# ASM2028.net
KiCad netlist of a schematic drawn in EAGLE
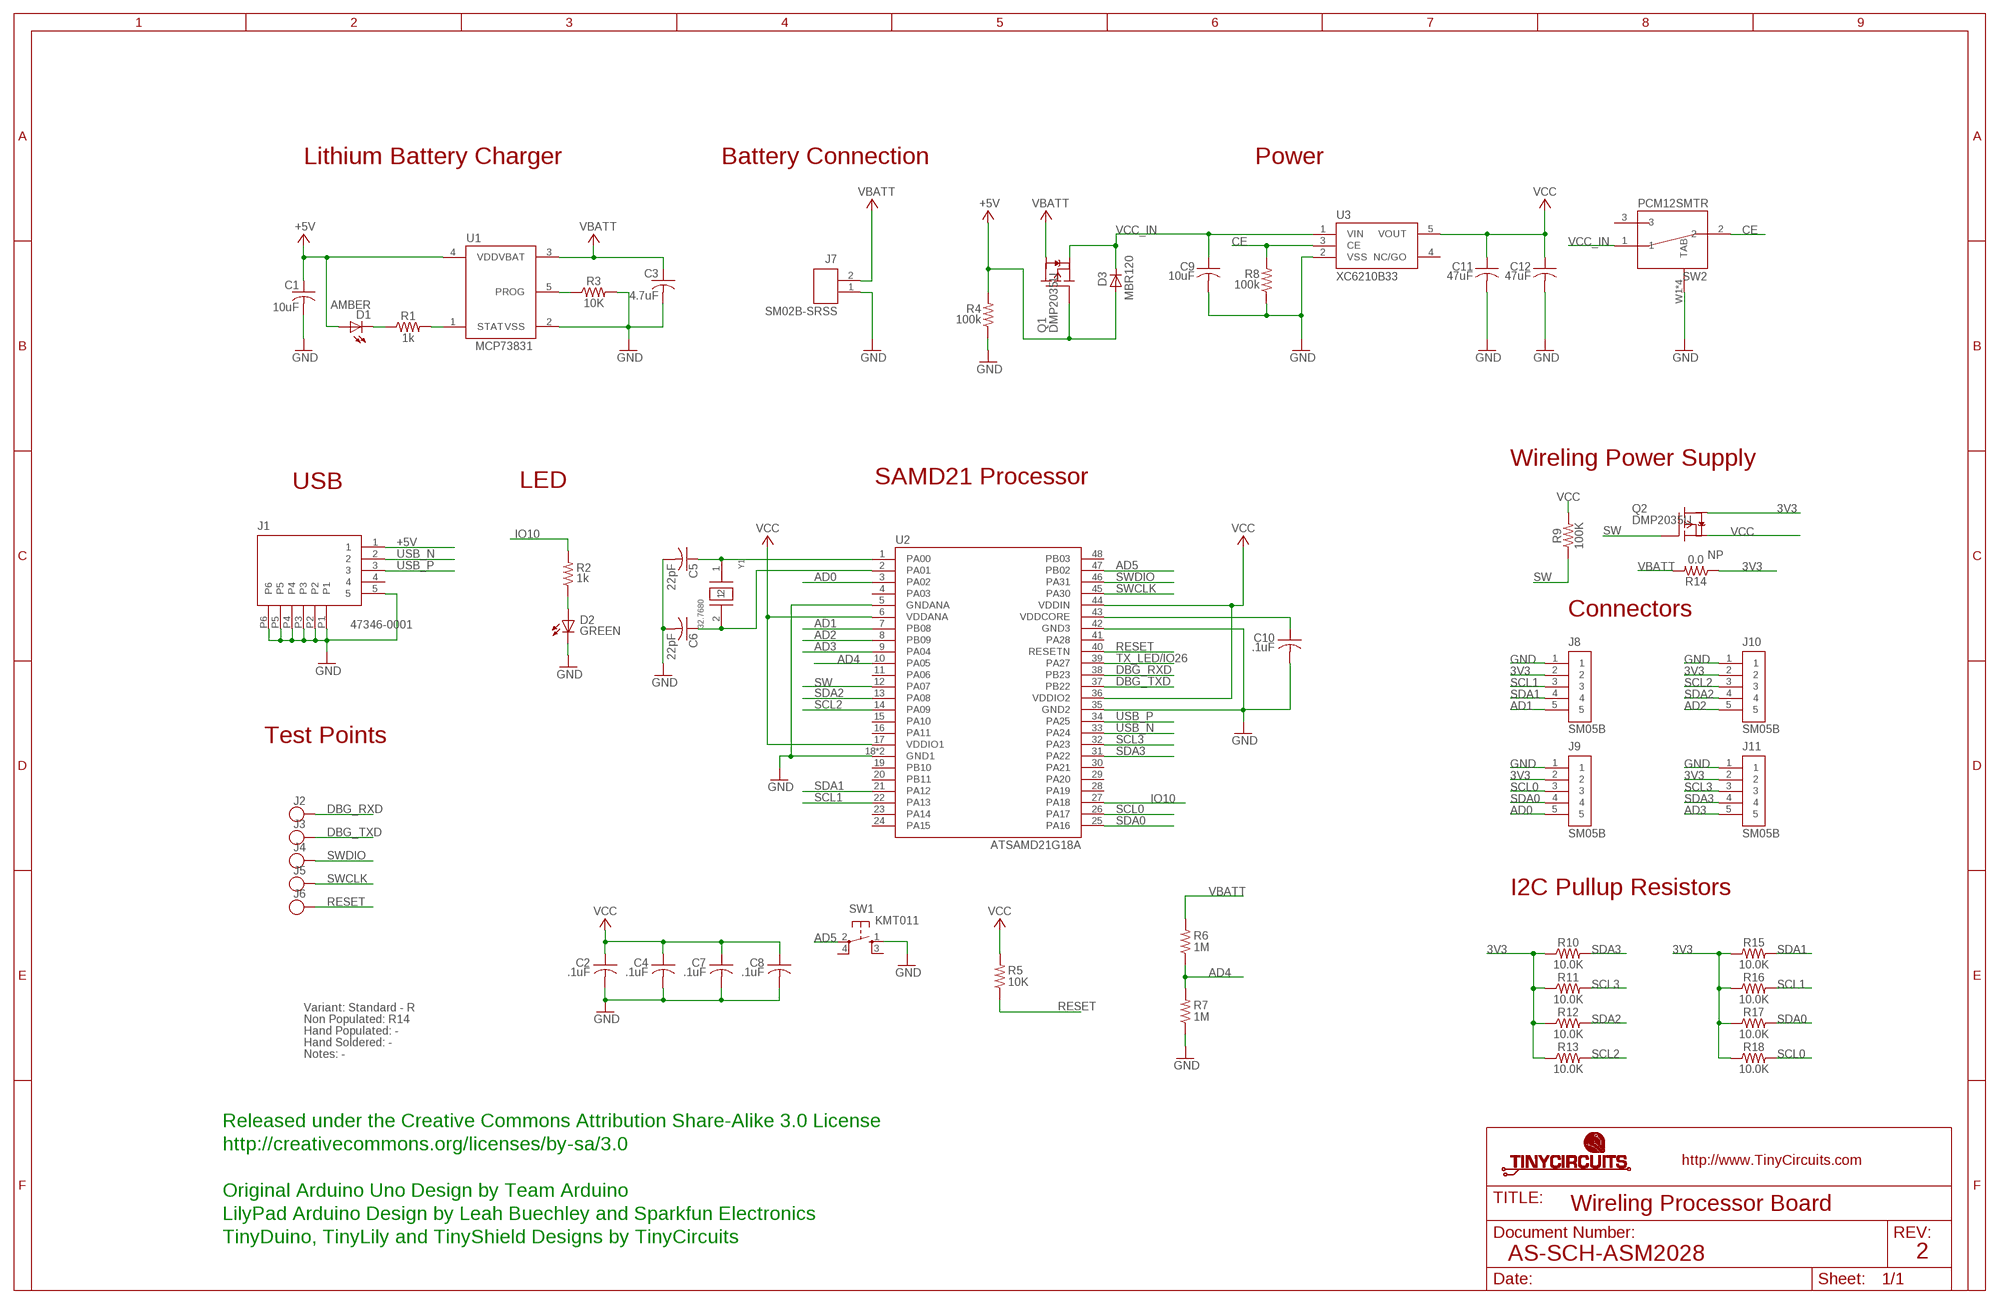
[diagram p0: schematic, sheet 1]

(export (version "E")
  (design (tool "Eeschema 10.0.6"))
  (components
    (comp (ref "C1")
      (value "10uF")
      (footprint "eagle-import:C0603")
      (fields (field (name "PARTNO") "AS-ITM-00002") (field (name "PARTNO_1") "AS-ITM-00002"))
      (libsource (lib "eagle-import") (part "AS-ITM-00002"))
    )
    (comp (ref "C2")
      (value ".1uF")
      (footprint "eagle-import:C0402")
      (fields (field (name "PARTNO") "AS-ITM-00008") (field (name "PARTNO_1") "AS-ITM-00008"))
      (libsource (lib "eagle-import") (part "AS-ITM-00008"))
    )
    (comp (ref "C3")
      (value "4.7uF")
      (footprint "eagle-import:C0603")
      (fields (field (name "PARTNO") "AS-ITM-00088") (field (name "PARTNO_1") "AS-ITM-00088"))
      (libsource (lib "eagle-import") (part "AS-ITM-00088"))
    )
    (comp (ref "C4")
      (value ".1uF")
      (footprint "eagle-import:C0402")
      (fields (field (name "PARTNO") "AS-ITM-00008") (field (name "PARTNO_1") "AS-ITM-00008"))
      (libsource (lib "eagle-import") (part "AS-ITM-00008"))
    )
    (comp (ref "C5")
      (value "22pF")
      (footprint "eagle-import:C0402")
      (fields (field (name "PARTNO") "AS-ITM-00211") (field (name "PARTNO_1") "AS-ITM-00211"))
      (libsource (lib "eagle-import") (part "AS-ITM-00211"))
    )
    (comp (ref "C6")
      (value "22pF")
      (footprint "eagle-import:C0402")
      (fields (field (name "PARTNO") "AS-ITM-00211") (field (name "PARTNO_1") "AS-ITM-00211"))
      (libsource (lib "eagle-import") (part "AS-ITM-00211"))
    )
    (comp (ref "C7")
      (value ".1uF")
      (footprint "eagle-import:C0402")
      (fields (field (name "PARTNO") "AS-ITM-00008") (field (name "PARTNO_1") "AS-ITM-00008"))
      (libsource (lib "eagle-import") (part "AS-ITM-00008"))
    )
    (comp (ref "C8")
      (value ".1uF")
      (footprint "eagle-import:C0402")
      (fields (field (name "PARTNO") "AS-ITM-00008") (field (name "PARTNO_1") "AS-ITM-00008"))
      (libsource (lib "eagle-import") (part "AS-ITM-00008"))
    )
    (comp (ref "C9")
      (value "10uF")
      (footprint "eagle-import:C0603")
      (fields (field (name "PARTNO") "AS-ITM-00002") (field (name "PARTNO_1") "AS-ITM-00002"))
      (libsource (lib "eagle-import") (part "AS-ITM-00002"))
    )
    (comp (ref "C10")
      (value ".1uF")
      (footprint "eagle-import:C0402")
      (fields (field (name "PARTNO") "AS-ITM-00008") (field (name "PARTNO_1") "AS-ITM-00008"))
      (libsource (lib "eagle-import") (part "AS-ITM-00008"))
    )
    (comp (ref "C11")
      (value "47uF")
      (footprint "eagle-import:C0603")
      (fields (field (name "PARTNO") "AS-ITM-00558") (field (name "PARTNO_1") "AS-ITM-00558"))
      (libsource (lib "eagle-import") (part "AS-ITM-00558"))
    )
    (comp (ref "C12")
      (value "47uF")
      (footprint "eagle-import:C0603")
      (fields (field (name "PARTNO") "AS-ITM-00558") (field (name "PARTNO_1") "AS-ITM-00558"))
      (libsource (lib "eagle-import") (part "AS-ITM-00558"))
    )
    (comp (ref "D1")
      (value "AMBER")
      (footprint "eagle-import:0402_LED")
      (fields (field (name "PARTNO") "AS-ITM-00058") (field (name "PARTNO_1") "AS-ITM-00058"))
      (libsource (lib "eagle-import") (part "AS-ITM-00058"))
    )
    (comp (ref "D2")
      (value "GREEN")
      (footprint "eagle-import:0402_LED")
      (fields
        (field (name "PARTNO") "AS-ITM-00038")
        (field (name "PARTNO_1") "AS-ITM-00038")
        (field (name "PNPROTATION") "0")
      )
      (libsource (lib "eagle-import") (part "AS-ITM-00038"))
    )
    (comp (ref "D3")
      (value "MBR120")
      (footprint "eagle-import:SOD-123FL")
      (fields (field (name "PARTNO") "AS-ITM-00111"))
      (libsource (lib "eagle-import") (part "AS-ITM-00111"))
    )
    (comp (ref "J1")
      (value "47346-0001")
      (footprint "eagle-import:MICRO_USB")
      (fields (field (name "PARTNO") "AS-ITM-00021"))
      (libsource (lib "eagle-import") (part "AS-ITM-00021"))
    )
    (comp (ref "J2")
      (value "TEST_POINT")
      (footprint "eagle-import:TEST_POINT_1MM")
      (libsource (lib "eagle-import") (part "TEST_POINT"))
    )
    (comp (ref "J3")
      (value "TEST_POINT")
      (footprint "eagle-import:TEST_POINT_1MM")
      (libsource (lib "eagle-import") (part "TEST_POINT"))
    )
    (comp (ref "J4")
      (value "TEST_POINT")
      (footprint "eagle-import:TEST_POINT_1MM")
      (libsource (lib "eagle-import") (part "TEST_POINT"))
    )
    (comp (ref "J5")
      (value "TEST_POINT")
      (footprint "eagle-import:TEST_POINT_1MM")
      (libsource (lib "eagle-import") (part "TEST_POINT"))
    )
    (comp (ref "J6")
      (value "TEST_POINT")
      (footprint "eagle-import:TEST_POINT_1MM")
      (libsource (lib "eagle-import") (part "TEST_POINT"))
    )
    (comp (ref "J7")
      (value "SM02B-SRSS")
      (footprint "eagle-import:JST_SH_2X1")
      (fields (field (name "PARTNO") "AS-ITM-00231"))
      (libsource (lib "eagle-import") (part "AS-ITM-00231"))
    )
    (comp (ref "J8")
      (value "SM05B")
      (footprint "eagle-import:JST_SH_5X1_EDGE")
      (fields (field (name "PARTNO") "AS-ITM-00340"))
      (libsource (lib "eagle-import") (part "AS-ITM-00340EDGE"))
    )
    (comp (ref "J9")
      (value "SM05B")
      (footprint "eagle-import:JST_SH_5X1_EDGE")
      (fields (field (name "PARTNO") "AS-ITM-00340"))
      (libsource (lib "eagle-import") (part "AS-ITM-00340EDGE"))
    )
    (comp (ref "J10")
      (value "SM05B")
      (footprint "eagle-import:JST_SH_5X1_EDGE")
      (fields (field (name "PARTNO") "AS-ITM-00340"))
      (libsource (lib "eagle-import") (part "AS-ITM-00340EDGE"))
    )
    (comp (ref "J11")
      (value "SM05B")
      (footprint "eagle-import:JST_SH_5X1_EDGE")
      (fields (field (name "PARTNO") "AS-ITM-00340"))
      (libsource (lib "eagle-import") (part "AS-ITM-00340EDGE"))
    )
    (comp (ref "Q1")
      (value "DMP2035U")
      (footprint "eagle-import:SOT23A")
      (fields (field (name "PARTNO") "AS-ITM-00024"))
      (libsource (lib "eagle-import") (part "AS-ITM-00024A"))
    )
    (comp (ref "Q2")
      (value "DMP2035U")
      (footprint "eagle-import:SOT23A")
      (fields (field (name "PARTNO") "AS-ITM-00024") (field (name "PARTNO_1") "AS-ITM-00024"))
      (libsource (lib "eagle-import") (part "AS-ITM-00024A"))
    )
    (comp (ref "R1")
      (value "1k")
      (footprint "eagle-import:0402")
      (fields (field (name "PARTNO") "AS-ITM-00003") (field (name "PARTNO_1") "AS-ITM-00003"))
      (libsource (lib "eagle-import") (part "AS-ITM-00003"))
    )
    (comp (ref "R2")
      (value "1k")
      (footprint "eagle-import:0402")
      (fields (field (name "PARTNO") "AS-ITM-00003") (field (name "PARTNO_1") "AS-ITM-00003"))
      (libsource (lib "eagle-import") (part "AS-ITM-00003"))
    )
    (comp (ref "R3")
      (value "10K")
      (footprint "eagle-import:0402")
      (fields (field (name "PARTNO") "AS-ITM-00032"))
      (libsource (lib "eagle-import") (part "AS-ITM-00032"))
    )
    (comp (ref "R4")
      (value "100k")
      (footprint "eagle-import:0402")
      (fields (field (name "PARTNO") "AS-ITM-00004") (field (name "PARTNO_1") "AS-ITM-00004"))
      (libsource (lib "eagle-import") (part "AS-ITM-00004"))
    )
    (comp (ref "R5")
      (value "10K")
      (footprint "eagle-import:0402")
      (fields (field (name "PARTNO") "AS-ITM-00032") (field (name "PARTNO_1") "AS-ITM-00032"))
      (libsource (lib "eagle-import") (part "AS-ITM-00032"))
    )
    (comp (ref "R6")
      (value "1M")
      (footprint "eagle-import:0402")
      (fields (field (name "PARTNO") "AS-ITM-00005") (field (name "PARTNO_1") "AS-ITM-00005"))
      (libsource (lib "eagle-import") (part "AS-ITM-00005"))
    )
    (comp (ref "R7")
      (value "1M")
      (footprint "eagle-import:0402")
      (fields (field (name "PARTNO") "AS-ITM-00005") (field (name "PARTNO_1") "AS-ITM-00005"))
      (libsource (lib "eagle-import") (part "AS-ITM-00005"))
    )
    (comp (ref "R8")
      (value "100k")
      (footprint "eagle-import:0402")
      (fields (field (name "PARTNO") "AS-ITM-00004") (field (name "PARTNO_1") "AS-ITM-00004"))
      (libsource (lib "eagle-import") (part "AS-ITM-00004"))
    )
    (comp (ref "R9")
      (value "100K")
      (footprint "eagle-import:0402")
      (fields (field (name "PARTNO") "AS-ITM-00004"))
      (libsource (lib "eagle-import") (part "AS-ITM-00004"))
    )
    (comp (ref "R10")
      (value "10.0K")
      (footprint "eagle-import:0402")
      (fields (field (name "PARTNO") "AS-ITM-00032"))
      (libsource (lib "eagle-import") (part "AS-ITM-00032"))
    )
    (comp (ref "R11")
      (value "10.0K")
      (footprint "eagle-import:0402")
      (fields (field (name "PARTNO") "AS-ITM-00032"))
      (libsource (lib "eagle-import") (part "AS-ITM-00032"))
    )
    (comp (ref "R12")
      (value "10.0K")
      (footprint "eagle-import:0402")
      (fields (field (name "PARTNO") "AS-ITM-00032"))
      (libsource (lib "eagle-import") (part "AS-ITM-00032"))
    )
    (comp (ref "R13")
      (value "10.0K")
      (footprint "eagle-import:0402")
      (fields (field (name "PARTNO") "AS-ITM-00032"))
      (libsource (lib "eagle-import") (part "AS-ITM-00032"))
    )
    (comp (ref "R14")
      (value "0.0")
      (footprint "eagle-import:0402")
      (fields (field (name "PARTNO") "AS-ITM-00076") (field (name "PARTNO_1") "AS-ITM-00076"))
      (libsource (lib "eagle-import") (part "AS-ITM-00076"))
    )
    (comp (ref "R15")
      (value "10.0K")
      (footprint "eagle-import:0402")
      (fields (field (name "PARTNO") "AS-ITM-00032"))
      (libsource (lib "eagle-import") (part "AS-ITM-00032"))
    )
    (comp (ref "R16")
      (value "10.0K")
      (footprint "eagle-import:0402")
      (fields (field (name "PARTNO") "AS-ITM-00032"))
      (libsource (lib "eagle-import") (part "AS-ITM-00032"))
    )
    (comp (ref "R17")
      (value "10.0K")
      (footprint "eagle-import:0402")
      (fields (field (name "PARTNO") "AS-ITM-00032"))
      (libsource (lib "eagle-import") (part "AS-ITM-00032"))
    )
    (comp (ref "R18")
      (value "10.0K")
      (footprint "eagle-import:0402")
      (fields (field (name "PARTNO") "AS-ITM-00032"))
      (libsource (lib "eagle-import") (part "AS-ITM-00032"))
    )
    (comp (ref "SW1")
      (value "KMT011")
      (footprint "eagle-import:KMT011")
      (fields (field (name "PARTNO") "AS-ITM-00041"))
      (libsource (lib "eagle-import") (part "AS-ITM-00041"))
    )
    (comp (ref "SW2")
      (value "PCM12SMTR")
      (footprint "eagle-import:PCM12SMTR")
      (fields (field (name "PARTNO") "AS-ITM-00220"))
      (libsource (lib "eagle-import") (part "AS-ITM-00220"))
    )
    (comp (ref "U1")
      (value "MCP73831")
      (footprint "eagle-import:SOT-23")
      (fields (field (name "PARTNO") "AS-ITM-00136"))
      (libsource (lib "eagle-import") (part "AS-ITM-00136"))
    )
    (comp (ref "U2")
      (value "ATSAMD21G18A")
      (footprint "eagle-import:QFN48")
      (fields (field (name "PARTNO") "AS-ITM-00273") (field (name "PARTNO_1") "AS-ITM-00273"))
      (libsource (lib "eagle-import") (part "AS-ITM-00273"))
    )
    (comp (ref "U3")
      (value "XC6210B33")
      (footprint "eagle-import:SOT-25")
      (fields (field (name "PARTNO") "AS-ITM-00046"))
      (libsource (lib "eagle-import") (part "AS-ITM-00046"))
    )
    (comp (ref "Y1")
      (value "32.7680")
      (footprint "eagle-import:ABS06")
      (fields (field (name "PARTNO") "AS-ITM-00279") (field (name "PARTNO_1") "AS-ITM-00279"))
      (libsource (lib "eagle-import") (part "AS-ITM-00279"))
    )
  )
  (nets
    (net (code "1") (name "+5V") (class "Default")
      (node (ref "C1") (pin "1") (pinfunction "1_1") (pintype "passive"))
      (node (ref "D1") (pin "1") (pinfunction "A_1") (pintype "passive"))
      (node (ref "D3") (pin "A") (pinfunction "A_A") (pintype "passive"))
      (node (ref "J1") (pin "1") (pinfunction "1_1") (pintype "bidirectional"))
      (node (ref "Q1") (pin "B") (pinfunction "G_B") (pintype "passive"))
      (node (ref "R4") (pin "2") (pinfunction "2_2") (pintype "passive"))
      (node (ref "U1") (pin "4") (pinfunction "VDD_4") (pintype "bidirectional"))
    )
    (net (code "2") (name "/3V3") (class "Default")
      (node (ref "J10") (pin "2") (pinfunction "2_2") (pintype "bidirectional"))
      (node (ref "J11") (pin "2") (pinfunction "2_2") (pintype "bidirectional"))
      (node (ref "J8") (pin "2") (pinfunction "2_2") (pintype "bidirectional"))
      (node (ref "J9") (pin "2") (pinfunction "2_2") (pintype "bidirectional"))
      (node (ref "Q2") (pin "C") (pinfunction "D_C") (pintype "passive"))
      (node (ref "R10") (pin "1") (pinfunction "1_1") (pintype "passive"))
      (node (ref "R11") (pin "1") (pinfunction "1_1") (pintype "passive"))
      (node (ref "R12") (pin "1") (pinfunction "1_1") (pintype "passive"))
      (node (ref "R13") (pin "1") (pinfunction "1_1") (pintype "passive"))
      (node (ref "R14") (pin "1") (pinfunction "1_1") (pintype "passive"))
      (node (ref "R15") (pin "1") (pinfunction "1_1") (pintype "passive"))
      (node (ref "R16") (pin "1") (pinfunction "1_1") (pintype "passive"))
      (node (ref "R17") (pin "1") (pinfunction "1_1") (pintype "passive"))
      (node (ref "R18") (pin "1") (pinfunction "1_1") (pintype "passive"))
    )
    (net (code "3") (name "/AD0") (class "Default")
      (node (ref "J9") (pin "5") (pinfunction "5_5") (pintype "bidirectional"))
      (node (ref "U2") (pin "3") (pinfunction "PA02_3") (pintype "bidirectional"))
    )
    (net (code "4") (name "/AD1") (class "Default")
      (node (ref "J8") (pin "5") (pinfunction "5_5") (pintype "bidirectional"))
      (node (ref "U2") (pin "7") (pinfunction "PB08_7") (pintype "bidirectional"))
    )
    (net (code "5") (name "/AD2") (class "Default")
      (node (ref "J10") (pin "5") (pinfunction "5_5") (pintype "bidirectional"))
      (node (ref "U2") (pin "8") (pinfunction "PB09_8") (pintype "bidirectional"))
    )
    (net (code "6") (name "/AD3") (class "Default")
      (node (ref "J11") (pin "5") (pinfunction "5_5") (pintype "bidirectional"))
      (node (ref "U2") (pin "9") (pinfunction "PA04_9") (pintype "bidirectional"))
    )
    (net (code "7") (name "/AD4") (class "Default")
      (node (ref "R6") (pin "1") (pinfunction "1_1") (pintype "passive"))
      (node (ref "R7") (pin "2") (pinfunction "2_2") (pintype "passive"))
      (node (ref "U2") (pin "10") (pinfunction "PA05_10") (pintype "bidirectional"))
    )
    (net (code "8") (name "/AD5") (class "Default")
      (node (ref "SW1") (pin "2") (pinfunction "2_2") (pintype "passive"))
      (node (ref "U2") (pin "47") (pinfunction "PB02_47") (pintype "bidirectional"))
    )
    (net (code "9") (name "/CE") (class "Default")
      (node (ref "R8") (pin "2") (pinfunction "2_2") (pintype "passive"))
      (node (ref "SW2") (pin "2") (pinfunction "2_2") (pintype "bidirectional"))
      (node (ref "U3") (pin "3") (pinfunction "CE_3") (pintype "bidirectional"))
    )
    (net (code "10") (name "/DBG_RXD") (class "Default")
      (node (ref "J2") (pin "P$1") (pinfunction "1_P$1") (pintype "bidirectional"))
      (node (ref "U2") (pin "38") (pinfunction "PB23_38") (pintype "bidirectional"))
    )
    (net (code "11") (name "/DBG_TXD") (class "Default")
      (node (ref "J3") (pin "P$1") (pinfunction "1_P$1") (pintype "bidirectional"))
      (node (ref "U2") (pin "37") (pinfunction "PB22_37") (pintype "bidirectional"))
    )
    (net (code "12") (name "/IO10") (class "Default")
      (node (ref "R2") (pin "2") (pinfunction "2_2") (pintype "passive"))
      (node (ref "U2") (pin "27") (pinfunction "PA18_27") (pintype "bidirectional"))
    )
    (net (code "13") (name "/RESET") (class "Default")
      (node (ref "J6") (pin "P$1") (pinfunction "1_P$1") (pintype "bidirectional"))
      (node (ref "R5") (pin "1") (pinfunction "1_1") (pintype "passive"))
      (node (ref "U2") (pin "40") (pinfunction "RESETN_40") (pintype "bidirectional"))
    )
    (net (code "14") (name "/SCL0") (class "Default")
      (node (ref "J9") (pin "3") (pinfunction "3_3") (pintype "bidirectional"))
      (node (ref "R18") (pin "2") (pinfunction "2_2") (pintype "passive"))
      (node (ref "U2") (pin "26") (pinfunction "PA17_26") (pintype "bidirectional"))
    )
    (net (code "15") (name "/SCL1") (class "Default")
      (node (ref "J8") (pin "3") (pinfunction "3_3") (pintype "bidirectional"))
      (node (ref "R16") (pin "2") (pinfunction "2_2") (pintype "passive"))
      (node (ref "U2") (pin "22") (pinfunction "PA13_22") (pintype "bidirectional"))
    )
    (net (code "16") (name "/SCL2") (class "Default")
      (node (ref "J10") (pin "3") (pinfunction "3_3") (pintype "bidirectional"))
      (node (ref "R13") (pin "2") (pinfunction "2_2") (pintype "passive"))
      (node (ref "U2") (pin "14") (pinfunction "PA09_14") (pintype "bidirectional"))
    )
    (net (code "17") (name "/SCL3") (class "Default")
      (node (ref "J11") (pin "3") (pinfunction "3_3") (pintype "bidirectional"))
      (node (ref "R11") (pin "2") (pinfunction "2_2") (pintype "passive"))
      (node (ref "U2") (pin "32") (pinfunction "PA23_32") (pintype "bidirectional"))
    )
    (net (code "18") (name "/SDA0") (class "Default")
      (node (ref "J9") (pin "4") (pinfunction "4_4") (pintype "bidirectional"))
      (node (ref "R17") (pin "2") (pinfunction "2_2") (pintype "passive"))
      (node (ref "U2") (pin "25") (pinfunction "PA16_25") (pintype "bidirectional"))
    )
    (net (code "19") (name "/SDA1") (class "Default")
      (node (ref "J8") (pin "4") (pinfunction "4_4") (pintype "bidirectional"))
      (node (ref "R15") (pin "2") (pinfunction "2_2") (pintype "passive"))
      (node (ref "U2") (pin "21") (pinfunction "PA12_21") (pintype "bidirectional"))
    )
    (net (code "20") (name "/SDA2") (class "Default")
      (node (ref "J10") (pin "4") (pinfunction "4_4") (pintype "bidirectional"))
      (node (ref "R12") (pin "2") (pinfunction "2_2") (pintype "passive"))
      (node (ref "U2") (pin "13") (pinfunction "PA08_13") (pintype "bidirectional"))
    )
    (net (code "21") (name "/SDA3") (class "Default")
      (node (ref "J11") (pin "4") (pinfunction "4_4") (pintype "bidirectional"))
      (node (ref "R10") (pin "2") (pinfunction "2_2") (pintype "passive"))
      (node (ref "U2") (pin "31") (pinfunction "PA22_31") (pintype "bidirectional"))
    )
    (net (code "22") (name "/SW") (class "Default")
      (node (ref "Q2") (pin "B") (pinfunction "G_B") (pintype "passive"))
      (node (ref "R9") (pin "1") (pinfunction "1_1") (pintype "passive"))
      (node (ref "U2") (pin "12") (pinfunction "PA07_12") (pintype "bidirectional"))
    )
    (net (code "23") (name "/SWCLK") (class "Default")
      (node (ref "J5") (pin "P$1") (pinfunction "1_P$1") (pintype "bidirectional"))
      (node (ref "U2") (pin "45") (pinfunction "PA30_45") (pintype "bidirectional"))
    )
    (net (code "24") (name "/SWDIO") (class "Default")
      (node (ref "J4") (pin "P$1") (pinfunction "1_P$1") (pintype "bidirectional"))
      (node (ref "U2") (pin "46") (pinfunction "PA31_46") (pintype "bidirectional"))
    )
    (net (code "25") (name "/TX_LED{slash}IO26") (class "Default")
      (node (ref "U2") (pin "39") (pinfunction "PA27_39") (pintype "bidirectional"))
    )
    (net (code "26") (name "/USB_N") (class "Default")
      (node (ref "J1") (pin "2") (pinfunction "2_2") (pintype "bidirectional"))
      (node (ref "U2") (pin "33") (pinfunction "PA24_33") (pintype "bidirectional"))
    )
    (net (code "27") (name "/USB_P") (class "Default")
      (node (ref "J1") (pin "3") (pinfunction "3_3") (pintype "bidirectional"))
      (node (ref "U2") (pin "34") (pinfunction "PA25_34") (pintype "bidirectional"))
    )
    (net (code "28") (name "/VCC_IN") (class "Default")
      (node (ref "C9") (pin "1") (pinfunction "1_1") (pintype "passive"))
      (node (ref "D3") (pin "C") (pinfunction "C_C") (pintype "passive"))
      (node (ref "Q1") (pin "E") (pinfunction "S_E") (pintype "passive"))
      (node (ref "SW2") (pin "1") (pinfunction "1_1") (pintype "bidirectional"))
      (node (ref "U3") (pin "1") (pinfunction "VIN_1") (pintype "bidirectional"))
    )
    (net (code "29") (name "GND") (class "Default")
      (node (ref "C1") (pin "2") (pinfunction "2_2") (pintype "passive"))
      (node (ref "C10") (pin "2") (pinfunction "2_2") (pintype "passive"))
      (node (ref "C11") (pin "2") (pinfunction "2_2") (pintype "passive"))
      (node (ref "C12") (pin "2") (pinfunction "2_2") (pintype "passive"))
      (node (ref "C2") (pin "2") (pinfunction "2_2") (pintype "passive"))
      (node (ref "C3") (pin "2") (pinfunction "2_2") (pintype "passive"))
      (node (ref "C4") (pin "2") (pinfunction "2_2") (pintype "passive"))
      (node (ref "C5") (pin "2") (pinfunction "2_2") (pintype "passive"))
      (node (ref "C6") (pin "2") (pinfunction "2_2") (pintype "passive"))
      (node (ref "C7") (pin "2") (pinfunction "2_2") (pintype "passive"))
      (node (ref "C8") (pin "2") (pinfunction "2_2") (pintype "passive"))
      (node (ref "C9") (pin "2") (pinfunction "2_2") (pintype "passive"))
      (node (ref "D2") (pin "2") (pinfunction "C_2") (pintype "passive"))
      (node (ref "J1") (pin "5") (pinfunction "5_5") (pintype "bidirectional"))
      (node (ref "J1") (pin "P1") (pinfunction "P1_P1") (pintype "bidirectional"))
      (node (ref "J1") (pin "P2") (pinfunction "P2_P2") (pintype "bidirectional"))
      (node (ref "J1") (pin "P3") (pinfunction "P3_P3") (pintype "bidirectional"))
      (node (ref "J1") (pin "P4") (pinfunction "P4_P4") (pintype "bidirectional"))
      (node (ref "J1") (pin "P5") (pinfunction "P5_P5") (pintype "bidirectional"))
      (node (ref "J1") (pin "P6") (pinfunction "P6_P6") (pintype "bidirectional"))
      (node (ref "J10") (pin "1") (pinfunction "1_1") (pintype "bidirectional"))
      (node (ref "J11") (pin "1") (pinfunction "1_1") (pintype "bidirectional"))
      (node (ref "J7") (pin "1") (pinfunction "2_1") (pintype "bidirectional"))
      (node (ref "J8") (pin "1") (pinfunction "1_1") (pintype "bidirectional"))
      (node (ref "J9") (pin "1") (pinfunction "1_1") (pintype "bidirectional"))
      (node (ref "R3") (pin "2") (pinfunction "2_2") (pintype "passive"))
      (node (ref "R4") (pin "1") (pinfunction "1_1") (pintype "passive"))
      (node (ref "R7") (pin "1") (pinfunction "1_1") (pintype "passive"))
      (node (ref "R8") (pin "1") (pinfunction "1_1") (pintype "passive"))
      (node (ref "SW1") (pin "1") (pinfunction "1_1") (pintype "passive"))
      (node (ref "SW2") (pin "W1") (pinfunction "TAB_W1") (pintype "bidirectional"))
      (node (ref "SW2") (pin "W2") (pinfunction "TAB_W2") (pintype "bidirectional"))
      (node (ref "SW2") (pin "W3") (pinfunction "TAB_W3") (pintype "bidirectional"))
      (node (ref "SW2") (pin "W4") (pinfunction "TAB_W4") (pintype "bidirectional"))
      (node (ref "U1") (pin "2") (pinfunction "VSS_2") (pintype "bidirectional"))
      (node (ref "U2") (pin "18") (pinfunction "GND1_18") (pintype "bidirectional"))
      (node (ref "U2") (pin "35") (pinfunction "GND2_35") (pintype "bidirectional"))
      (node (ref "U2") (pin "42") (pinfunction "GND3_42") (pintype "bidirectional"))
      (node (ref "U2") (pin "5") (pinfunction "GNDANA_5") (pintype "bidirectional"))
      (node (ref "U2") (pin "EXP") (pinfunction "GND1_EXP") (pintype "bidirectional"))
      (node (ref "U3") (pin "2") (pinfunction "VSS_2") (pintype "power_in"))
    )
    (net (code "30") (name "Net-(D1-C)") (class "Default")
      (node (ref "D1") (pin "2") (pinfunction "C_2") (pintype "passive"))
      (node (ref "R1") (pin "1") (pinfunction "1_1") (pintype "passive"))
    )
    (net (code "31") (name "Net-(D2-A)") (class "Default")
      (node (ref "D2") (pin "1") (pinfunction "A_1") (pintype "passive"))
      (node (ref "R2") (pin "1") (pinfunction "1_1") (pintype "passive"))
    )
    (net (code "32") (name "Net-(U1-PROG)") (class "Default")
      (node (ref "R3") (pin "1") (pinfunction "1_1") (pintype "passive"))
      (node (ref "U1") (pin "5") (pinfunction "PROG_5") (pintype "bidirectional"))
    )
    (net (code "33") (name "Net-(U1-STAT)") (class "Default")
      (node (ref "R1") (pin "2") (pinfunction "2_2") (pintype "passive"))
      (node (ref "U1") (pin "1") (pinfunction "STAT_1") (pintype "bidirectional"))
    )
    (net (code "34") (name "Net-(U2-PA00)") (class "Default")
      (node (ref "C5") (pin "1") (pinfunction "1_1") (pintype "passive"))
      (node (ref "U2") (pin "1") (pinfunction "PA00_1") (pintype "bidirectional"))
      (node (ref "Y1") (pin "1") (pinfunction "1_1") (pintype "bidirectional"))
    )
    (net (code "35") (name "Net-(U2-PA01)") (class "Default")
      (node (ref "C6") (pin "1") (pinfunction "1_1") (pintype "passive"))
      (node (ref "U2") (pin "2") (pinfunction "PA01_2") (pintype "bidirectional"))
      (node (ref "Y1") (pin "2") (pinfunction "2_2") (pintype "bidirectional"))
    )
    (net (code "36") (name "Net-(U2-VDDCORE)") (class "Default")
      (node (ref "C10") (pin "1") (pinfunction "1_1") (pintype "passive"))
      (node (ref "U2") (pin "43") (pinfunction "VDDCORE_43") (pintype "bidirectional"))
    )
    (net (code "37") (name "VBATT") (class "Default")
      (node (ref "C3") (pin "1") (pinfunction "1_1") (pintype "passive"))
      (node (ref "J7") (pin "2") (pinfunction "1_2") (pintype "bidirectional"))
      (node (ref "Q1") (pin "C") (pinfunction "D_C") (pintype "passive"))
      (node (ref "R14") (pin "2") (pinfunction "2_2") (pintype "passive"))
      (node (ref "R6") (pin "2") (pinfunction "2_2") (pintype "passive"))
      (node (ref "U1") (pin "3") (pinfunction "VBAT_3") (pintype "bidirectional"))
    )
    (net (code "38") (name "VCC") (class "Default")
      (node (ref "C11") (pin "1") (pinfunction "1_1") (pintype "passive"))
      (node (ref "C12") (pin "1") (pinfunction "1_1") (pintype "passive"))
      (node (ref "C2") (pin "1") (pinfunction "1_1") (pintype "passive"))
      (node (ref "C4") (pin "1") (pinfunction "1_1") (pintype "passive"))
      (node (ref "C7") (pin "1") (pinfunction "1_1") (pintype "passive"))
      (node (ref "C8") (pin "1") (pinfunction "1_1") (pintype "passive"))
      (node (ref "Q2") (pin "E") (pinfunction "S_E") (pintype "passive"))
      (node (ref "R5") (pin "2") (pinfunction "2_2") (pintype "passive"))
      (node (ref "R9") (pin "2") (pinfunction "2_2") (pintype "passive"))
      (node (ref "U2") (pin "17") (pinfunction "VDDIO1_17") (pintype "bidirectional"))
      (node (ref "U2") (pin "36") (pinfunction "VDDIO2_36") (pintype "bidirectional"))
      (node (ref "U2") (pin "44") (pinfunction "VDDIN_44") (pintype "bidirectional"))
      (node (ref "U2") (pin "6") (pinfunction "VDDANA_6") (pintype "bidirectional"))
      (node (ref "U3") (pin "5") (pinfunction "VOUT_5") (pintype "bidirectional"))
    )
    (net (code "39") (name "unconnected-(J1-Pad4)") (class "Default")
      (node (ref "J1") (pin "4") (pinfunction "4_4") (pintype "bidirectional"))
    )
    (net (code "40") (name "unconnected-(SW1-Pad3)") (class "Default")
      (node (ref "SW1") (pin "3") (pinfunction "3_3") (pintype "passive"))
    )
    (net (code "41") (name "unconnected-(SW1-Pad4)") (class "Default")
      (node (ref "SW1") (pin "4") (pinfunction "4_4") (pintype "passive"))
    )
    (net (code "42") (name "unconnected-(SW2-Pad3)") (class "Default")
      (node (ref "SW2") (pin "3") (pinfunction "3_3") (pintype "bidirectional"))
    )
    (net (code "43") (name "unconnected-(U2-PA03-Pad4)") (class "Default")
      (node (ref "U2") (pin "4") (pinfunction "PA03_4") (pintype "bidirectional"))
    )
    (net (code "44") (name "unconnected-(U2-PA06-Pad11)") (class "Default")
      (node (ref "U2") (pin "11") (pinfunction "PA06_11") (pintype "bidirectional"))
    )
    (net (code "45") (name "unconnected-(U2-PA10-Pad15)") (class "Default")
      (node (ref "U2") (pin "15") (pinfunction "PA10_15") (pintype "bidirectional"))
    )
    (net (code "46") (name "unconnected-(U2-PA11-Pad16)") (class "Default")
      (node (ref "U2") (pin "16") (pinfunction "PA11_16") (pintype "bidirectional"))
    )
    (net (code "47") (name "unconnected-(U2-PA14-Pad23)") (class "Default")
      (node (ref "U2") (pin "23") (pinfunction "PA14_23") (pintype "bidirectional"))
    )
    (net (code "48") (name "unconnected-(U2-PA15-Pad24)") (class "Default")
      (node (ref "U2") (pin "24") (pinfunction "PA15_24") (pintype "bidirectional"))
    )
    (net (code "49") (name "unconnected-(U2-PA19-Pad28)") (class "Default")
      (node (ref "U2") (pin "28") (pinfunction "PA19_28") (pintype "bidirectional"))
    )
    (net (code "50") (name "unconnected-(U2-PA20-Pad29)") (class "Default")
      (node (ref "U2") (pin "29") (pinfunction "PA20_29") (pintype "bidirectional"))
    )
    (net (code "51") (name "unconnected-(U2-PA21-Pad30)") (class "Default")
      (node (ref "U2") (pin "30") (pinfunction "PA21_30") (pintype "bidirectional"))
    )
    (net (code "52") (name "unconnected-(U2-PA28-Pad41)") (class "Default")
      (node (ref "U2") (pin "41") (pinfunction "PA28_41") (pintype "bidirectional"))
    )
    (net (code "53") (name "unconnected-(U2-PB03-Pad48)") (class "Default")
      (node (ref "U2") (pin "48") (pinfunction "PB03_48") (pintype "bidirectional"))
    )
    (net (code "54") (name "unconnected-(U2-PB10-Pad19)") (class "Default")
      (node (ref "U2") (pin "19") (pinfunction "PB10_19") (pintype "bidirectional"))
    )
    (net (code "55") (name "unconnected-(U2-PB11-Pad20)") (class "Default")
      (node (ref "U2") (pin "20") (pinfunction "PB11_20") (pintype "bidirectional"))
    )
    (net (code "56") (name "unconnected-(U3-NC{slash}GO-Pad4)") (class "Default")
      (node (ref "U3") (pin "4") (pinfunction "NC/GO_4") (pintype "bidirectional"))
    )
  )
)
